# SCH_555-Chaser_2025-10-31.net
KiCad netlist of a schematic drawn in EasyEDA
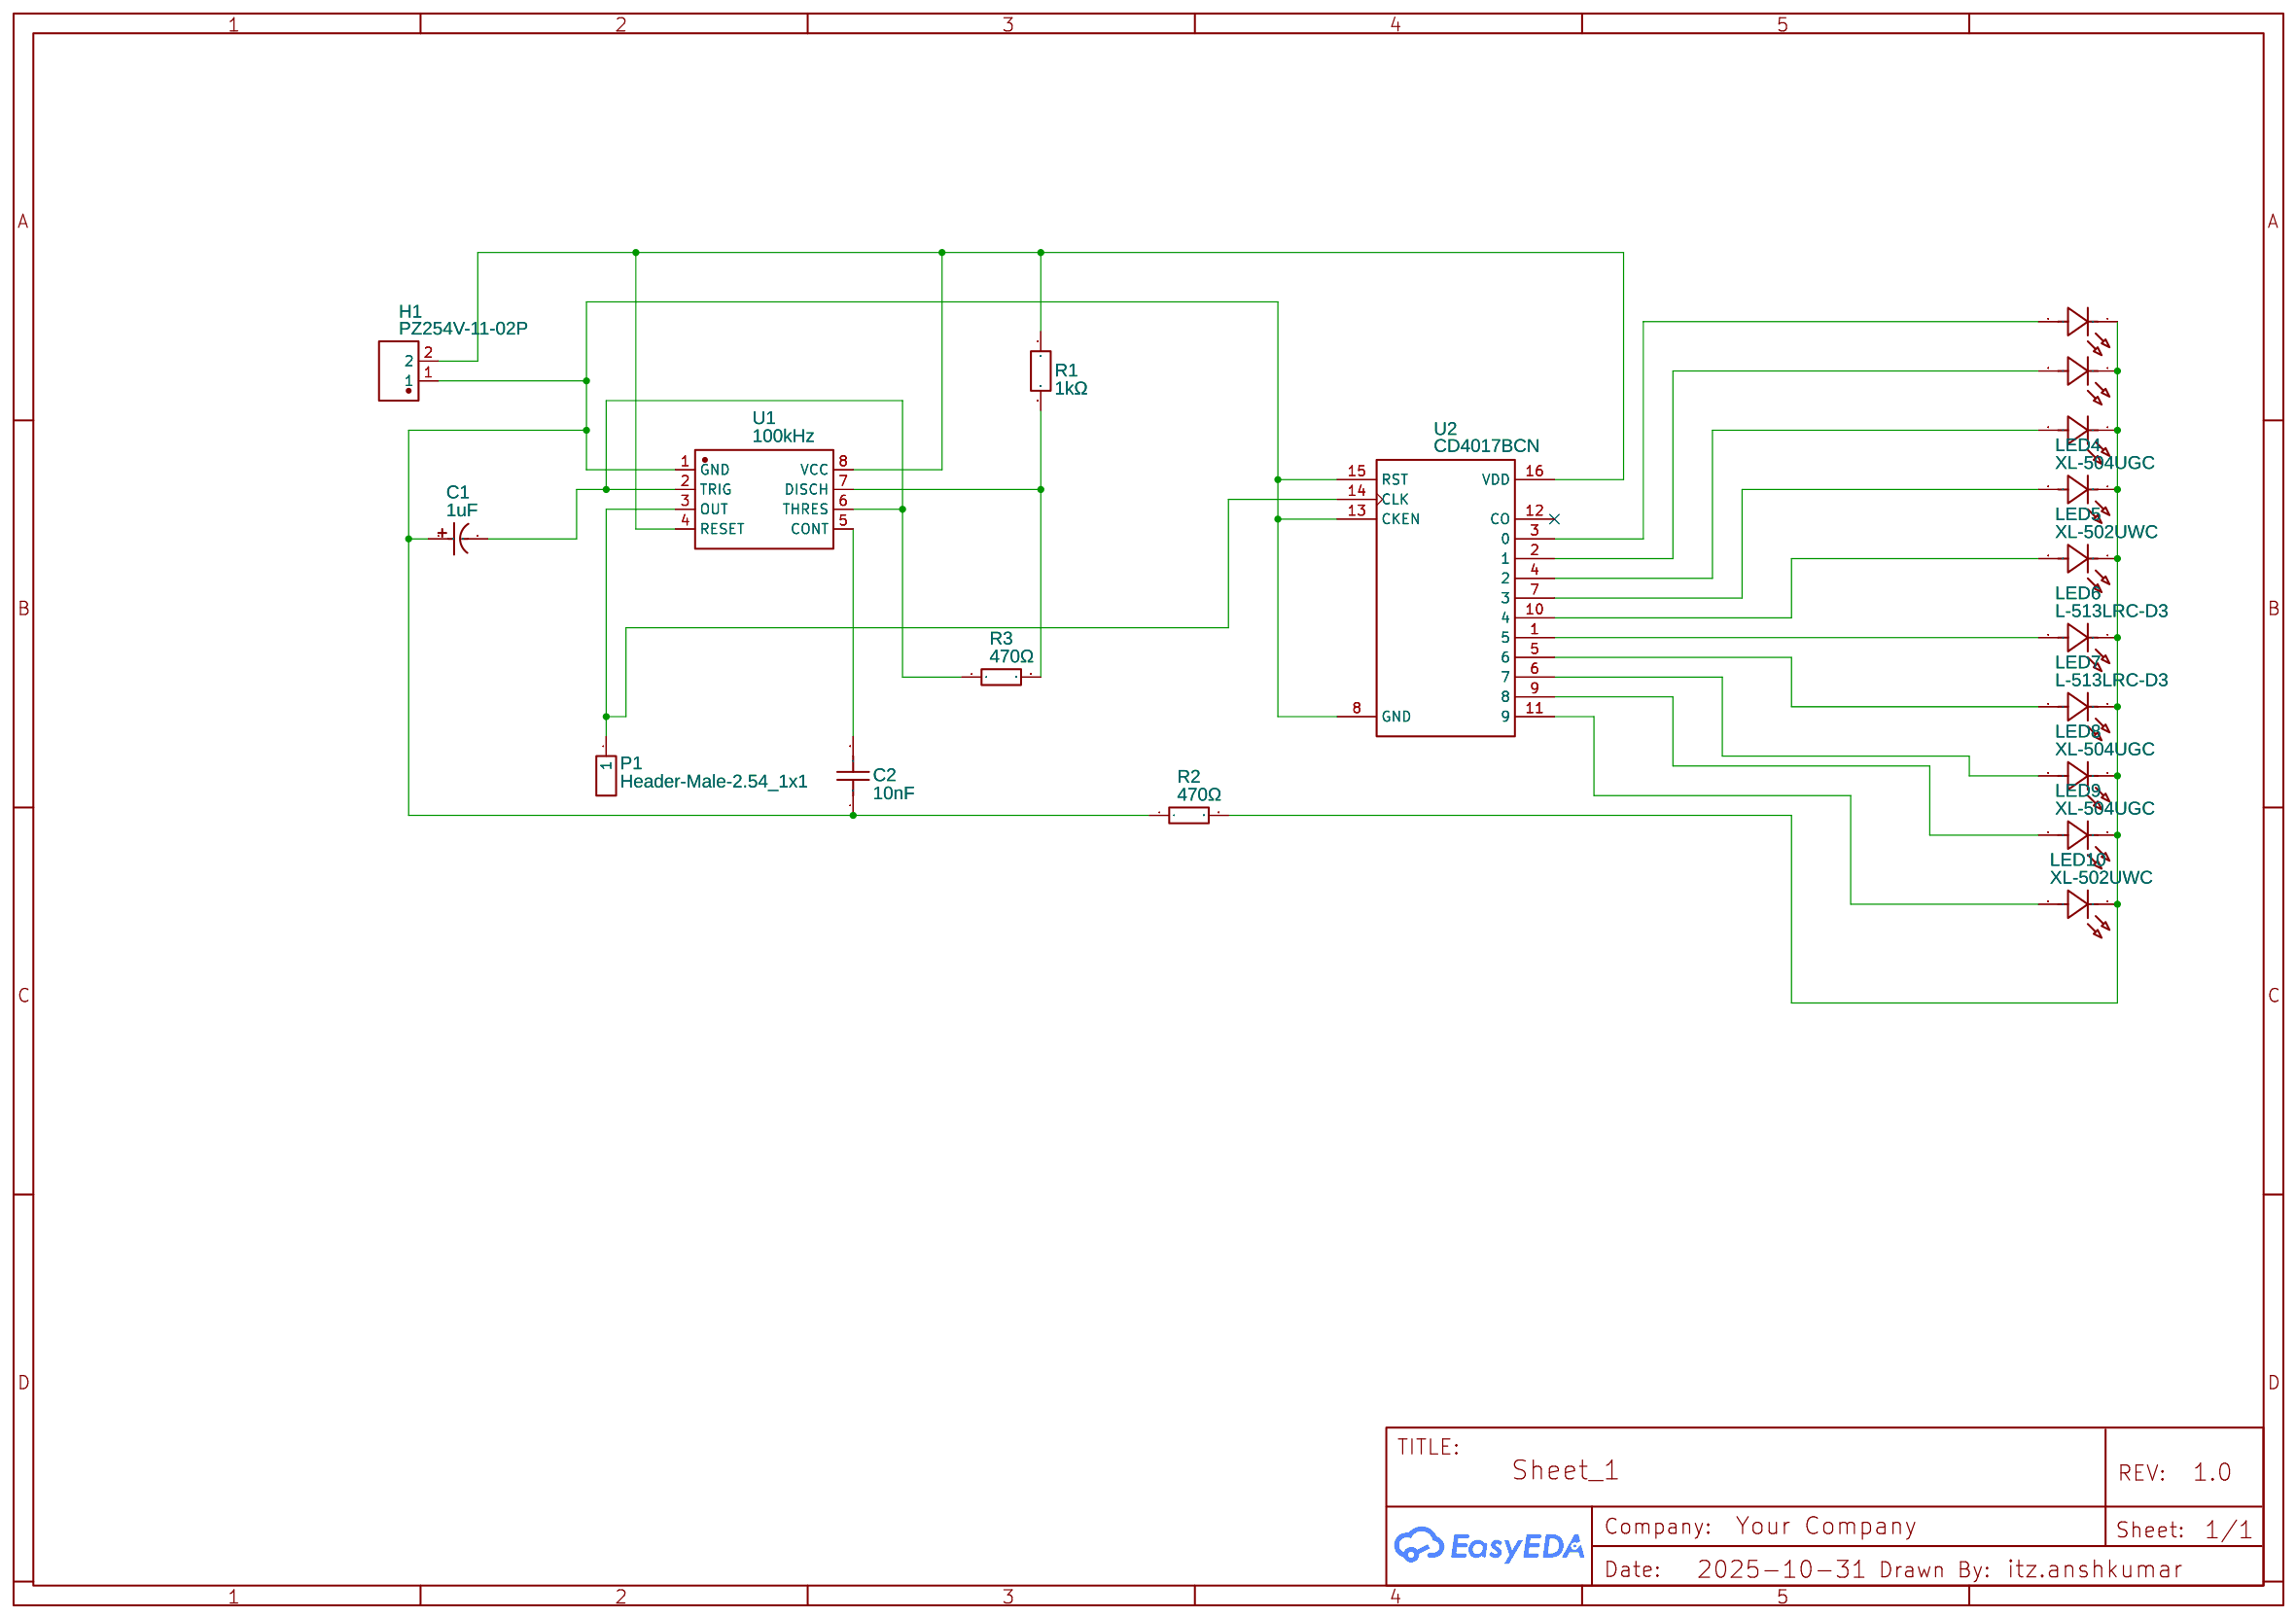
[diagram p0: schematic sheet]

(export (version "E")
  (design (tool "Eeschema 10.0.6"))
  (components
    (comp (ref "C1")
      (value "1uF")
      (fields (field (name "Manufacturer Part") "KF010M050C110A") (field (name "Manufacturer") "CapXon(丰宾)"))
      (libsource (lib "") (part "KF010M050C110A"))
    )
    (comp (ref "C2")
      (value "10nF")
      (fields (field (name "Manufacturer Part") "N09F1B103MN0B0S0N0") (field (name "Manufacturer") "STE(松田)"))
      (libsource (lib "") (part "N09F1B103MN0B0S0N0"))
    )
    (comp (ref "H1")
      (value "PZ254V-11-02P")
      (fields (field (name "Manufacturer") "XFCN(兴飞)"))
      (libsource (lib "") (part "PZ254V-11-02P"))
    )
    (comp (ref "LED1")
      (value "L-513LRC-D3")
      (fields (field (name "Manufacturer") "PARALIGHT(光鼎)"))
      (libsource (lib "") (part "L-513LRC-D3"))
    )
    (comp (ref "LED2")
      (value "TZ-L2-05YYBO3TDJ15-001")
      (fields (field (name "Manufacturer") "TUOZHAN(拓展光电)"))
      (libsource (lib "") (part "TZ-L2-05YYBO3TDJ15-001"))
    )
    (comp (ref "LED3")
      (value "TJ-L5FYTXHTCGLFLC9Y-A5")
      (fields (field (name "Manufacturer") "TOGIALED(统佳)"))
      (libsource (lib "") (part "TJ-L5FYTXHTCGLFLC9Y-A5"))
    )
    (comp (ref "LED4")
      (value "XL-504UGC")
      (fields (field (name "Manufacturer") "XINGLIGHT(成兴光)"))
      (libsource (lib "") (part "XL-504UGC"))
    )
    (comp (ref "LED5")
      (value "XL-502UWC")
      (fields (field (name "Manufacturer") "XINGLIGHT(成兴光)"))
      (libsource (lib "") (part "XL-502UWC"))
    )
    (comp (ref "LED6")
      (value "L-513LRC-D3")
      (fields (field (name "Manufacturer") "PARALIGHT(光鼎)"))
      (libsource (lib "") (part "L-513LRC-D3"))
    )
    (comp (ref "LED7")
      (value "L-513LRC-D3")
      (fields (field (name "Manufacturer") "PARALIGHT(光鼎)"))
      (libsource (lib "") (part "L-513LRC-D3"))
    )
    (comp (ref "LED8")
      (value "XL-504UGC")
      (fields (field (name "Manufacturer") "XINGLIGHT(成兴光)"))
      (libsource (lib "") (part "XL-504UGC"))
    )
    (comp (ref "LED9")
      (value "XL-504UGC")
      (fields (field (name "Manufacturer") "XINGLIGHT(成兴光)"))
      (libsource (lib "") (part "XL-504UGC"))
    )
    (comp (ref "LED10")
      (value "XL-502UWC")
      (fields (field (name "Manufacturer") "XINGLIGHT(成兴光)"))
      (libsource (lib "") (part "XL-502UWC"))
    )
    (comp (ref "P1")
      (value "Header-Male-2.54_1x1")
      (fields (field (name "Manufacturer Part") "2.54-1*1P针") (field (name "Manufacturer") "BOOMELE(博穆精密)"))
      (libsource (lib "") (part "Header-Male-2.54_1x1"))
    )
    (comp (ref "R1")
      (value "1kΩ")
      (fields (field (name "Manufacturer Part") "MF1/4W-1KΩ±1%T52") (field (name "Manufacturer") "华星机电"))
      (libsource (lib "") (part "MF1/4W-1KΩ±1%T52"))
    )
    (comp (ref "R2")
      (value "470Ω")
      (fields
        (field (name "Manufacturer Part") "MFR0W4F4700A50")
        (field (name "Manufacturer") "UNI-ROYAL(厚声)")
      )
      (libsource (lib "") (part "MFR0W4F4700A50"))
    )
    (comp (ref "R3")
      (value "470Ω")
      (fields
        (field (name "Manufacturer Part") "MFR0W4F4700A50")
        (field (name "Manufacturer") "UNI-ROYAL(厚声)")
      )
      (libsource (lib "") (part "MFR0W4F4700A50"))
    )
    (comp (ref "U1")
      (value "100kHz")
      (fields (field (name "Manufacturer Part") "NE555P") (field (name "Manufacturer") "TI(德州仪器)"))
      (libsource (lib "") (part "NE555P"))
    )
    (comp (ref "U2") (value "CD4017BCN") (libsource (lib "") (part "CD4017BCN")))
  )
  (nets
    (net (code "1") (name "Net-(LED1-A)") (class "Default")
      (node (ref "LED1") (pin "2") (pinfunction "A_2") (pintype "unspecified"))
      (node (ref "U2") (pin "3") (pinfunction "0_3") (pintype "output"))
    )
    (net (code "2") (name "Net-(LED1-K)") (class "Default")
      (node (ref "LED1") (pin "1") (pinfunction "K_1") (pintype "unspecified"))
      (node (ref "LED10") (pin "1") (pinfunction "K_1") (pintype "unspecified"))
      (node (ref "LED2") (pin "1") (pinfunction "-_1") (pintype "unspecified"))
      (node (ref "LED3") (pin "1") (pinfunction "-_1") (pintype "unspecified"))
      (node (ref "LED4") (pin "1") (pinfunction "K_1") (pintype "unspecified"))
      (node (ref "LED5") (pin "1") (pinfunction "K_1") (pintype "unspecified"))
      (node (ref "LED6") (pin "1") (pinfunction "K_1") (pintype "unspecified"))
      (node (ref "LED7") (pin "1") (pinfunction "K_1") (pintype "unspecified"))
      (node (ref "LED8") (pin "1") (pinfunction "K_1") (pintype "unspecified"))
      (node (ref "LED9") (pin "1") (pinfunction "K_1") (pintype "unspecified"))
      (node (ref "R2") (pin "2") (pinfunction "2_2") (pintype "input"))
    )
    (net (code "3") (name "Net-(LED2-+)") (class "Default")
      (node (ref "LED2") (pin "2") (pinfunction "+_2") (pintype "unspecified"))
      (node (ref "U2") (pin "2") (pinfunction "1_2") (pintype "output"))
    )
    (net (code "4") (name "Net-(LED3-+)") (class "Default")
      (node (ref "LED3") (pin "2") (pinfunction "+_2") (pintype "unspecified"))
      (node (ref "U2") (pin "4") (pinfunction "2_4") (pintype "output"))
    )
    (net (code "5") (name "Net-(LED4-A)") (class "Default")
      (node (ref "LED4") (pin "2") (pinfunction "A_2") (pintype "unspecified"))
      (node (ref "U2") (pin "7") (pinfunction "3_7") (pintype "output"))
    )
    (net (code "6") (name "Net-(LED5-A)") (class "Default")
      (node (ref "LED5") (pin "2") (pinfunction "A_2") (pintype "unspecified"))
      (node (ref "U2") (pin "10") (pinfunction "4_10") (pintype "output"))
    )
    (net (code "7") (name "Net-(LED6-A)") (class "Default")
      (node (ref "LED6") (pin "2") (pinfunction "A_2") (pintype "unspecified"))
      (node (ref "U2") (pin "1") (pinfunction "5_1") (pintype "output"))
    )
    (net (code "8") (name "Net-(LED7-A)") (class "Default")
      (node (ref "LED7") (pin "2") (pinfunction "A_2") (pintype "unspecified"))
      (node (ref "U2") (pin "5") (pinfunction "6_5") (pintype "output"))
    )
    (net (code "9") (name "Net-(LED8-A)") (class "Default")
      (node (ref "LED8") (pin "2") (pinfunction "A_2") (pintype "unspecified"))
      (node (ref "U2") (pin "6") (pinfunction "7_6") (pintype "output"))
    )
    (net (code "10") (name "Net-(LED9-A)") (class "Default")
      (node (ref "LED9") (pin "2") (pinfunction "A_2") (pintype "unspecified"))
      (node (ref "U2") (pin "9") (pinfunction "8_9") (pintype "output"))
    )
    (net (code "11") (name "Net-(LED10-A)") (class "Default")
      (node (ref "LED10") (pin "2") (pinfunction "A_2") (pintype "unspecified"))
      (node (ref "U2") (pin "11") (pinfunction "9_11") (pintype "output"))
    )
    (net (code "12") (name "Net-(U1-CONT)") (class "Default")
      (node (ref "C2") (pin "2") (pinfunction "2_2") (pintype "unspecified"))
      (node (ref "U1") (pin "5") (pinfunction "CONT_5") (pintype "unspecified"))
    )
    (net (code "13") (name "Net-(U1-DISCH)") (class "Default")
      (node (ref "R1") (pin "2") (pinfunction "2_2") (pintype "unspecified"))
      (node (ref "R3") (pin "2") (pinfunction "2_2") (pintype "input"))
      (node (ref "U1") (pin "7") (pinfunction "DISCH_7") (pintype "unspecified"))
    )
    (net (code "14") (name "Net-(U1-GND)") (class "Default")
      (node (ref "C1") (pin "1") (pinfunction "1_1") (pintype "input"))
      (node (ref "C2") (pin "1") (pinfunction "1_1") (pintype "unspecified"))
      (node (ref "H1") (pin "1") (pinfunction "1_1") (pintype "unspecified"))
      (node (ref "R2") (pin "1") (pinfunction "1_1") (pintype "input"))
      (node (ref "U1") (pin "1") (pinfunction "GND_1") (pintype "unspecified"))
      (node (ref "U2") (pin "13") (pinfunction "CKEN_13") (pintype "unspecified"))
      (node (ref "U2") (pin "15") (pinfunction "RST_15") (pintype "unspecified"))
      (node (ref "U2") (pin "8") (pinfunction "GND_8") (pintype "passive"))
    )
    (net (code "15") (name "Net-(U1-OUT)") (class "Default")
      (node (ref "P1") (pin "1") (pinfunction "1_1") (pintype "input"))
      (node (ref "U1") (pin "3") (pinfunction "OUT_3") (pintype "unspecified"))
      (node (ref "U2") (pin "14") (pinfunction "CLK_14") (pintype "unspecified"))
    )
    (net (code "16") (name "Net-(U1-RESET)") (class "Default")
      (node (ref "H1") (pin "2") (pinfunction "2_2") (pintype "unspecified"))
      (node (ref "R1") (pin "1") (pinfunction "1_1") (pintype "unspecified"))
      (node (ref "U1") (pin "4") (pinfunction "RESET_4") (pintype "unspecified"))
      (node (ref "U1") (pin "8") (pinfunction "VCC_8") (pintype "unspecified"))
      (node (ref "U2") (pin "16") (pinfunction "VDD_16") (pintype "passive"))
    )
    (net (code "17") (name "Net-(U1-THRES)") (class "Default")
      (node (ref "C1") (pin "2") (pinfunction "2_2") (pintype "input"))
      (node (ref "R3") (pin "1") (pinfunction "1_1") (pintype "input"))
      (node (ref "U1") (pin "2") (pinfunction "TRIG_2") (pintype "unspecified"))
      (node (ref "U1") (pin "6") (pinfunction "THRES_6") (pintype "unspecified"))
    )
    (net (code "18") (name "unconnected-(U2-CO-Pad12)") (class "Default")
      (node (ref "U2") (pin "12") (pinfunction "CO_12") (pintype "output+no_connect"))
    )
  )
)
